# micro.net
KiCad netlist of a schematic drawn in EAGLE
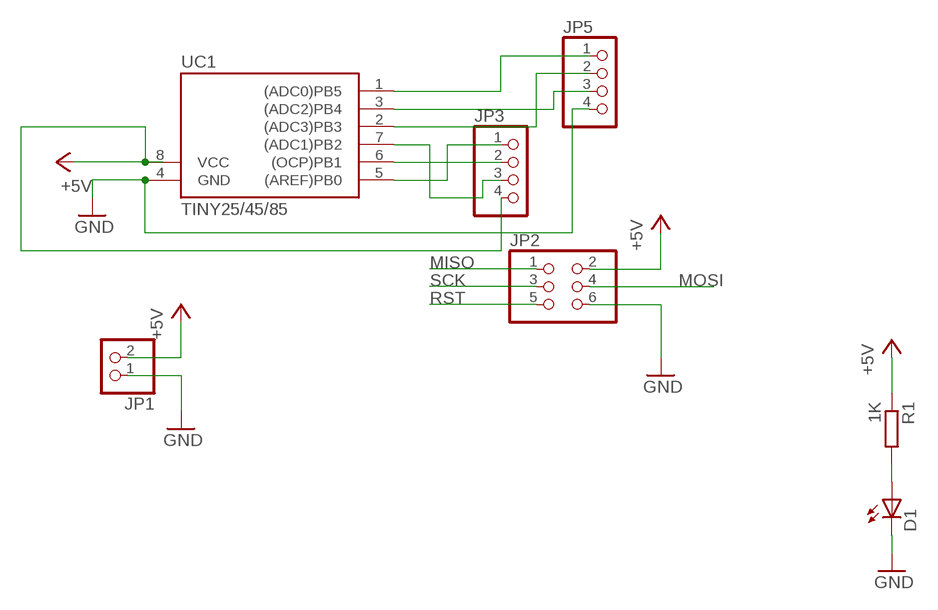
[diagram p0: schematic, sheet 1]

(export (version "E")
  (design (tool "Eeschema 10.0.6"))
  (components
    (comp (ref "D1")
      (value "LED3MM")
      (footprint "eagle-import:LED3MM")
      (libsource (lib "eagle-import") (part "LED3MM"))
    )
    (comp (ref "JP1")
      (value "PINHD-1X02_2.54")
      (footprint "eagle-import:1X02")
      (libsource (lib "eagle-import") (part "PINHD-1X02_2.54"))
    )
    (comp (ref "JP2")
      (value "PINHD-2X03_2.54")
      (footprint "eagle-import:2X03")
      (libsource (lib "eagle-import") (part "PINHD-2X03_2.54"))
    )
    (comp (ref "JP3")
      (value "PINHD-1X4")
      (footprint "eagle-import:1X04")
      (libsource (lib "eagle-import") (part "PINHD-1X4"))
    )
    (comp (ref "JP5")
      (value "PINHD-1X4")
      (footprint "eagle-import:1X04")
      (libsource (lib "eagle-import") (part "PINHD-1X4"))
    )
    (comp (ref "R1")
      (value "1K")
      (footprint "eagle-import:0207_2V")
      (libsource (lib "eagle-import") (part "R-EU_0207/2V"))
    )
    (comp (ref "UC1")
      (value "TINY25/45/85")
      (footprint "eagle-import:SOIC8")
      (libsource (lib "eagle-import") (part "TINY25-20SU"))
    )
  )
  (nets
    (net (code "1") (name "+5V") (class "Default")
      (node (ref "JP1") (pin "2") (pinfunction "2_2") (pintype "passive"))
      (node (ref "JP2") (pin "2") (pinfunction "2_2") (pintype "passive"))
      (node (ref "JP3") (pin "4") (pinfunction "4_4") (pintype "passive"))
      (node (ref "R1") (pin "1") (pinfunction "1_1") (pintype "passive"))
      (node (ref "UC1") (pin "8") (pinfunction "VCC_8") (pintype "power_in"))
    )
    (net (code "2") (name "/MISO") (class "Default")
      (node (ref "JP2") (pin "1") (pinfunction "1_1") (pintype "passive"))
      (node (ref "JP3") (pin "2") (pinfunction "2_2") (pintype "passive"))
      (node (ref "UC1") (pin "6") (pinfunction "(OCP)PB1_6") (pintype "bidirectional"))
    )
    (net (code "3") (name "/MOSI") (class "Default")
      (node (ref "JP2") (pin "4") (pinfunction "4_4") (pintype "passive"))
      (node (ref "JP3") (pin "1") (pinfunction "1_1") (pintype "passive"))
      (node (ref "UC1") (pin "5") (pinfunction "(AREF)PB0_5") (pintype "bidirectional"))
    )
    (net (code "4") (name "/RST") (class "Default")
      (node (ref "JP2") (pin "5") (pinfunction "5_5") (pintype "passive"))
      (node (ref "JP5") (pin "1") (pinfunction "1_1") (pintype "passive"))
      (node (ref "UC1") (pin "1") (pinfunction "(ADC0)PB5_1") (pintype "bidirectional"))
    )
    (net (code "5") (name "/SCK") (class "Default")
      (node (ref "JP2") (pin "3") (pinfunction "3_3") (pintype "passive"))
      (node (ref "JP3") (pin "3") (pinfunction "3_3") (pintype "passive"))
      (node (ref "UC1") (pin "7") (pinfunction "(ADC1)PB2_7") (pintype "bidirectional"))
    )
    (net (code "6") (name "GND") (class "Default")
      (node (ref "D1") (pin "K") (pinfunction "C_K") (pintype "passive"))
      (node (ref "JP1") (pin "1") (pinfunction "1_1") (pintype "passive"))
      (node (ref "JP2") (pin "6") (pinfunction "6_6") (pintype "passive"))
      (node (ref "JP5") (pin "4") (pinfunction "4_4") (pintype "passive"))
      (node (ref "UC1") (pin "4") (pinfunction "GND_4") (pintype "power_in"))
    )
    (net (code "7") (name "Net-(D1-PadA)") (class "Default")
      (node (ref "D1") (pin "A") (pinfunction "A_A") (pintype "passive"))
      (node (ref "R1") (pin "2") (pinfunction "2_2") (pintype "passive"))
    )
    (net (code "8") (name "Net-(UC1-(ADC2)PB4)") (class "Default")
      (node (ref "JP5") (pin "3") (pinfunction "3_3") (pintype "passive"))
      (node (ref "UC1") (pin "3") (pinfunction "(ADC2)PB4_3") (pintype "bidirectional"))
    )
    (net (code "9") (name "Net-(UC1-(ADC3)PB3)") (class "Default")
      (node (ref "JP5") (pin "2") (pinfunction "2_2") (pintype "passive"))
      (node (ref "UC1") (pin "2") (pinfunction "(ADC3)PB3_2") (pintype "bidirectional"))
    )
  )
)
